# shield-gps.net
KiCad netlist of a schematic drawn in EAGLE
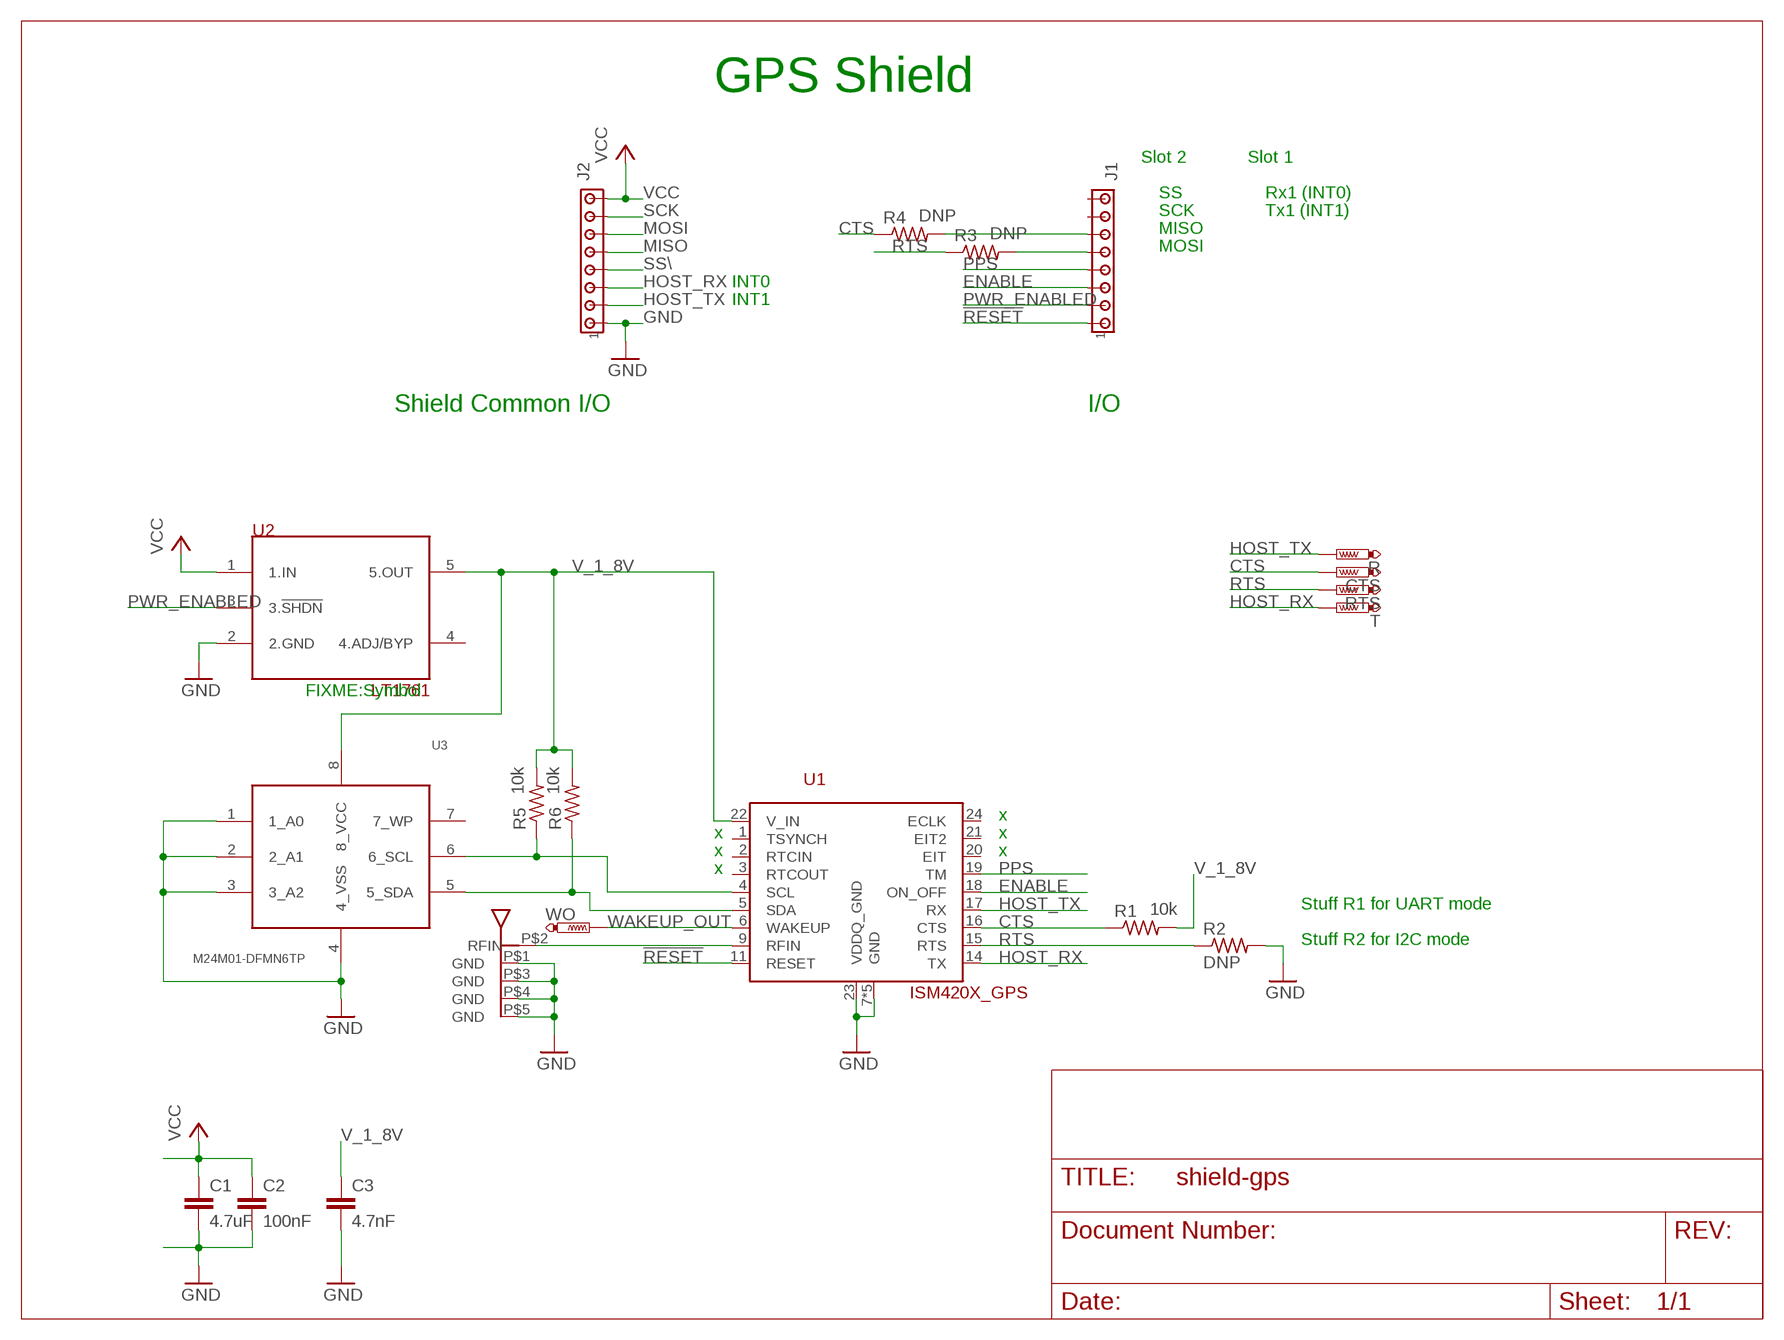
[diagram p0: schematic, sheet 1]

(export (version "E")
  (design (tool "Eeschema 10.0.6"))
  (components
    (comp (ref "ANT1")
      (value "A10204_ANTENNA")
      (footprint "eagle-import:A10204_ANTENNA")
      (libsource (lib "eagle-import") (part "A10204_ANTENNA"))
    )
    (comp (ref "C1")
      (value "4.7uF")
      (footprint "eagle-import:C0603")
      (libsource (lib "eagle-import") (part "C-EUC0603"))
    )
    (comp (ref "C2")
      (value "100nF")
      (footprint "eagle-import:C0603")
      (libsource (lib "eagle-import") (part "C-EUC0603"))
    )
    (comp (ref "C3")
      (value "4.7nF")
      (footprint "eagle-import:C0603")
      (libsource (lib "eagle-import") (part "C-EUC0603"))
    )
    (comp (ref "CTS")
      (value "PTR1PAD1-13")
      (footprint "eagle-import:P1-13")
      (libsource (lib "eagle-import") (part "PTR1PAD1-13"))
    )
    (comp (ref "J1")
      (value "MTA08-100")
      (footprint "eagle-import:10X08MTA")
      (libsource (lib "eagle-import") (part "MTA08-100"))
    )
    (comp (ref "J2")
      (value "MTA08-100")
      (footprint "eagle-import:10X08MTA")
      (libsource (lib "eagle-import") (part "MTA08-100"))
    )
    (comp (ref "R")
      (value "PTR1PAD1-13")
      (footprint "eagle-import:P1-13")
      (libsource (lib "eagle-import") (part "PTR1PAD1-13"))
    )
    (comp (ref "R1")
      (value "10k")
      (footprint "eagle-import:R0603")
      (libsource (lib "eagle-import") (part "R-US_R0603"))
    )
    (comp (ref "R2")
      (value "DNP")
      (footprint "eagle-import:R0603")
      (libsource (lib "eagle-import") (part "R-US_R0603"))
    )
    (comp (ref "R3")
      (value "DNP")
      (footprint "eagle-import:R0603")
      (libsource (lib "eagle-import") (part "R-US_R0603"))
    )
    (comp (ref "R4")
      (value "DNP")
      (footprint "eagle-import:R0603")
      (libsource (lib "eagle-import") (part "R-US_R0603"))
    )
    (comp (ref "R5")
      (value "10k")
      (footprint "eagle-import:R0603")
      (libsource (lib "eagle-import") (part "R-US_R0603"))
    )
    (comp (ref "R6")
      (value "10k")
      (footprint "eagle-import:R0603")
      (libsource (lib "eagle-import") (part "R-US_R0603"))
    )
    (comp (ref "RTS")
      (value "PTR1PAD1-13")
      (footprint "eagle-import:P1-13")
      (libsource (lib "eagle-import") (part "PTR1PAD1-13"))
    )
    (comp (ref "T")
      (value "PTR1PAD1-13")
      (footprint "eagle-import:P1-13")
      (libsource (lib "eagle-import") (part "PTR1PAD1-13"))
    )
    (comp (ref "U1")
      (value "ISM420X_GPS")
      (footprint "eagle-import:ISM420X_GPS")
      (libsource (lib "eagle-import") (part "ISM420X_GPS"))
    )
    (comp (ref "U2")
      (value "TC1016-1.85VCTTR")
      (footprint "eagle-import:SOT23-5")
      (libsource (lib "eagle-import") (part "VREG_LT1761_SOT23-5"))
    )
    (comp (ref "U3")
      (value "M24M01-DFMN6TP")
      (footprint "eagle-import:SO-8")
      (libsource (lib "eagle-import") (part "24AA1025"))
    )
    (comp (ref "WO")
      (value "PTR1PAD1-13")
      (footprint "eagle-import:P1-13")
      (libsource (lib "eagle-import") (part "PTR1PAD1-13"))
    )
  )
  (nets
    (net (code "1") (name "/CTS") (class "Default")
      (node (ref "CTS") (pin "TP") (pinfunction "TP_TP") (pintype "input"))
      (node (ref "R1") (pin "1") (pinfunction "1_1") (pintype "passive"))
      (node (ref "R4") (pin "1") (pinfunction "1_1") (pintype "passive"))
      (node (ref "U1") (pin "16") (pinfunction "CTS_16") (pintype "bidirectional"))
    )
    (net (code "2") (name "/ENABLE") (class "Default")
      (node (ref "J1") (pin "3") (pinfunction "3_3") (pintype "passive"))
      (node (ref "U1") (pin "18") (pinfunction "ON_OFF_18") (pintype "bidirectional"))
    )
    (net (code "3") (name "/HOST_RX") (class "Default")
      (node (ref "J2") (pin "3") (pinfunction "3_3") (pintype "passive"))
      (node (ref "T") (pin "TP") (pinfunction "TP_TP") (pintype "input"))
      (node (ref "U1") (pin "14") (pinfunction "TX_14") (pintype "bidirectional"))
    )
    (net (code "4") (name "/HOST_TX") (class "Default")
      (node (ref "J2") (pin "2") (pinfunction "2_2") (pintype "passive"))
      (node (ref "R") (pin "TP") (pinfunction "TP_TP") (pintype "input"))
      (node (ref "U1") (pin "17") (pinfunction "RX_17") (pintype "bidirectional"))
    )
    (net (code "5") (name "/MISO") (class "Default")
      (node (ref "J2") (pin "5") (pinfunction "5_5") (pintype "passive"))
    )
    (net (code "6") (name "/MOSI") (class "Default")
      (node (ref "J2") (pin "6") (pinfunction "6_6") (pintype "passive"))
    )
    (net (code "7") (name "/PPS") (class "Default")
      (node (ref "J1") (pin "4") (pinfunction "4_4") (pintype "passive"))
      (node (ref "U1") (pin "19") (pinfunction "TM_19") (pintype "bidirectional"))
    )
    (net (code "8") (name "/PWR_ENABLED") (class "Default")
      (node (ref "J1") (pin "2") (pinfunction "2_2") (pintype "passive"))
      (node (ref "U2") (pin "3") (pinfunction "3.~{SHDN}_3") (pintype "bidirectional"))
    )
    (net (code "9") (name "/RTS") (class "Default")
      (node (ref "R2") (pin "1") (pinfunction "1_1") (pintype "passive"))
      (node (ref "R3") (pin "1") (pinfunction "1_1") (pintype "passive"))
      (node (ref "RTS") (pin "TP") (pinfunction "TP_TP") (pintype "input"))
      (node (ref "U1") (pin "15") (pinfunction "RTS_15") (pintype "bidirectional"))
    )
    (net (code "10") (name "/SCK") (class "Default")
      (node (ref "J2") (pin "7") (pinfunction "7_7") (pintype "passive"))
    )
    (net (code "11") (name "/SS\\") (class "Default")
      (node (ref "J2") (pin "4") (pinfunction "4_4") (pintype "passive"))
    )
    (net (code "12") (name "/V_1_8V") (class "Default")
      (node (ref "C3") (pin "1") (pinfunction "1_1") (pintype "passive"))
      (node (ref "R1") (pin "2") (pinfunction "2_2") (pintype "passive"))
      (node (ref "R5") (pin "2") (pinfunction "2_2") (pintype "passive"))
      (node (ref "R6") (pin "2") (pinfunction "2_2") (pintype "passive"))
      (node (ref "U1") (pin "22") (pinfunction "V_IN_22") (pintype "bidirectional"))
      (node (ref "U2") (pin "5") (pinfunction "5.OUT_5") (pintype "bidirectional"))
      (node (ref "U3") (pin "8") (pinfunction "8_VCC_8") (pintype "power_in"))
    )
    (net (code "13") (name "/WAKEUP_OUT") (class "Default")
      (node (ref "U1") (pin "6") (pinfunction "WAKEUP_6") (pintype "bidirectional"))
      (node (ref "WO") (pin "TP") (pinfunction "TP_TP") (pintype "input"))
    )
    (net (code "14") (name "/~{RESET}") (class "Default")
      (node (ref "J1") (pin "1") (pinfunction "1_1") (pintype "passive"))
      (node (ref "U1") (pin "11") (pinfunction "RESET_11") (pintype "bidirectional"))
    )
    (net (code "15") (name "GND") (class "Default")
      (node (ref "ANT1") (pin "P$1") (pinfunction "GND_P$1") (pintype "power_in"))
      (node (ref "ANT1") (pin "P$3") (pinfunction "GND_P$3") (pintype "power_in"))
      (node (ref "ANT1") (pin "P$4") (pinfunction "GND_P$4") (pintype "power_in"))
      (node (ref "ANT1") (pin "P$5") (pinfunction "GND_P$5") (pintype "power_in"))
      (node (ref "C1") (pin "2") (pinfunction "2_2") (pintype "passive"))
      (node (ref "C2") (pin "2") (pinfunction "2_2") (pintype "passive"))
      (node (ref "C3") (pin "2") (pinfunction "2_2") (pintype "passive"))
      (node (ref "J2") (pin "1") (pinfunction "1_1") (pintype "passive"))
      (node (ref "R2") (pin "2") (pinfunction "2_2") (pintype "passive"))
      (node (ref "U1") (pin "10") (pinfunction "GND_10") (pintype "bidirectional"))
      (node (ref "U1") (pin "12") (pinfunction "GND_12") (pintype "bidirectional"))
      (node (ref "U1") (pin "13") (pinfunction "GND_13") (pintype "bidirectional"))
      (node (ref "U1") (pin "23") (pinfunction "VDDQ_GND_23") (pintype "bidirectional"))
      (node (ref "U1") (pin "7") (pinfunction "GND_7") (pintype "bidirectional"))
      (node (ref "U1") (pin "8") (pinfunction "GND_8") (pintype "bidirectional"))
      (node (ref "U2") (pin "2") (pinfunction "2.GND_2") (pintype "bidirectional"))
      (node (ref "U3") (pin "1") (pinfunction "1_A0_1") (pintype "bidirectional"))
      (node (ref "U3") (pin "2") (pinfunction "2_A1_2") (pintype "bidirectional"))
      (node (ref "U3") (pin "3") (pinfunction "3_A2_3") (pintype "bidirectional"))
      (node (ref "U3") (pin "4") (pinfunction "4_VSS_4") (pintype "power_in"))
    )
    (net (code "16") (name "Net-(ANT1-RFIN)") (class "Default")
      (node (ref "ANT1") (pin "P$2") (pinfunction "RFIN_P$2") (pintype "bidirectional"))
      (node (ref "U1") (pin "9") (pinfunction "RFIN_9") (pintype "bidirectional"))
    )
    (net (code "17") (name "Net-(J1-Pad5)") (class "Default")
      (node (ref "J1") (pin "5") (pinfunction "5_5") (pintype "passive"))
      (node (ref "R3") (pin "2") (pinfunction "2_2") (pintype "passive"))
    )
    (net (code "18") (name "Net-(J1-Pad6)") (class "Default")
      (node (ref "J1") (pin "6") (pinfunction "6_6") (pintype "passive"))
      (node (ref "R4") (pin "2") (pinfunction "2_2") (pintype "passive"))
    )
    (net (code "19") (name "Net-(U1-SCL)") (class "Default")
      (node (ref "R5") (pin "1") (pinfunction "1_1") (pintype "passive"))
      (node (ref "U1") (pin "4") (pinfunction "SCL_4") (pintype "bidirectional"))
      (node (ref "U3") (pin "6") (pinfunction "6_SCL_6") (pintype "bidirectional"))
    )
    (net (code "20") (name "Net-(U1-SDA)") (class "Default")
      (node (ref "R6") (pin "1") (pinfunction "1_1") (pintype "passive"))
      (node (ref "U1") (pin "5") (pinfunction "SDA_5") (pintype "bidirectional"))
      (node (ref "U3") (pin "5") (pinfunction "5_SDA_5") (pintype "bidirectional"))
    )
    (net (code "21") (name "VCC") (class "Default")
      (node (ref "C1") (pin "1") (pinfunction "1_1") (pintype "passive"))
      (node (ref "C2") (pin "1") (pinfunction "1_1") (pintype "passive"))
      (node (ref "J2") (pin "8") (pinfunction "8_8") (pintype "passive"))
      (node (ref "U2") (pin "1") (pinfunction "1.IN_1") (pintype "bidirectional"))
    )
    (net (code "22") (name "unconnected-(J1-Pad7)") (class "Default")
      (node (ref "J1") (pin "7") (pinfunction "7_7") (pintype "passive"))
    )
    (net (code "23") (name "unconnected-(J1-Pad8)") (class "Default")
      (node (ref "J1") (pin "8") (pinfunction "8_8") (pintype "passive"))
    )
    (net (code "24") (name "unconnected-(U1-ECLK-Pad24)") (class "Default")
      (node (ref "U1") (pin "24") (pinfunction "ECLK_24") (pintype "bidirectional"))
    )
    (net (code "25") (name "unconnected-(U1-EIT-Pad20)") (class "Default")
      (node (ref "U1") (pin "20") (pinfunction "EIT_20") (pintype "bidirectional"))
    )
    (net (code "26") (name "unconnected-(U1-EIT2-Pad21)") (class "Default")
      (node (ref "U1") (pin "21") (pinfunction "EIT2_21") (pintype "bidirectional"))
    )
    (net (code "27") (name "unconnected-(U1-RTCIN-Pad2)") (class "Default")
      (node (ref "U1") (pin "2") (pinfunction "RTCIN_2") (pintype "bidirectional"))
    )
    (net (code "28") (name "unconnected-(U1-RTCOUT-Pad3)") (class "Default")
      (node (ref "U1") (pin "3") (pinfunction "RTCOUT_3") (pintype "bidirectional"))
    )
    (net (code "29") (name "unconnected-(U1-TSYNCH-Pad1)") (class "Default")
      (node (ref "U1") (pin "1") (pinfunction "TSYNCH_1") (pintype "bidirectional"))
    )
    (net (code "30") (name "unconnected-(U2-4.ADJ{slash}BYP-Pad4)") (class "Default")
      (node (ref "U2") (pin "4") (pinfunction "4.ADJ/BYP_4") (pintype "bidirectional"))
    )
    (net (code "31") (name "unconnected-(U3-7_WP-Pad7)") (class "Default")
      (node (ref "U3") (pin "7") (pinfunction "7_WP_7") (pintype "bidirectional"))
    )
  )
)
